# Apple_DOS_extension_board_smaller.net
KiCad netlist of a schematic drawn in EAGLE
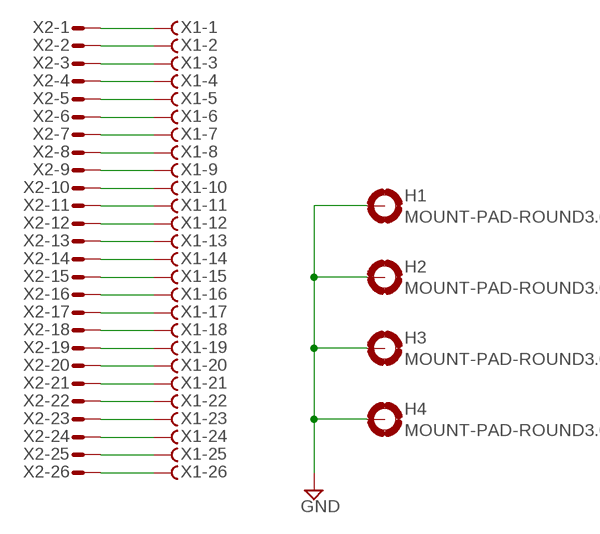
[diagram p0: schematic, sheet 1]

(export (version "E")
  (design (tool "Eeschema 10.0.6"))
  (components
    (comp (ref "H1")
      (value "MOUNT-PAD-ROUND3.6")
      (footprint "eagle-import:3,6-PAD")
      (libsource (lib "eagle-import") (part "MOUNT-PAD-ROUND3.6"))
    )
    (comp (ref "H2")
      (value "MOUNT-PAD-ROUND3.6")
      (footprint "eagle-import:3,6-PAD")
      (libsource (lib "eagle-import") (part "MOUNT-PAD-ROUND3.6"))
    )
    (comp (ref "H3")
      (value "MOUNT-PAD-ROUND3.6")
      (footprint "eagle-import:3,6-PAD")
      (libsource (lib "eagle-import") (part "MOUNT-PAD-ROUND3.6"))
    )
    (comp (ref "H4")
      (value "MOUNT-PAD-ROUND3.6")
      (footprint "eagle-import:3,6-PAD")
      (libsource (lib "eagle-import") (part "MOUNT-PAD-ROUND3.6"))
    )
    (comp (ref "X1")
      (value "HF26HS")
      (footprint "eagle-import:HDF26H")
      (libsource (lib "eagle-import") (part "HF26?SH"))
    )
    (comp (ref "X2")
      (value "HM26HS")
      (footprint "eagle-import:HDM26H")
      (libsource (lib "eagle-import") (part "HM26?SH"))
    )
  )
  (nets
    (net (code "1") (name "GND") (class "Default")
      (node (ref "H1") (pin "B3,6") (pinfunction "MOUNT_B3,6") (pintype "passive"))
      (node (ref "H2") (pin "B3,6") (pinfunction "MOUNT_B3,6") (pintype "passive"))
      (node (ref "H3") (pin "B3,6") (pinfunction "MOUNT_B3,6") (pintype "passive"))
      (node (ref "H4") (pin "B3,6") (pinfunction "MOUNT_B3,6") (pintype "passive"))
    )
    (net (code "2") (name "Net-(X1A-F)") (class "Default")
      (node (ref "X1") (pin "1") (pinfunction "F_1") (pintype "passive"))
      (node (ref "X2") (pin "1") (pinfunction "M_1") (pintype "passive"))
    )
    (net (code "3") (name "Net-(X1B-F)") (class "Default")
      (node (ref "X1") (pin "10") (pinfunction "F_10") (pintype "passive"))
      (node (ref "X2") (pin "10") (pinfunction "M_10") (pintype "passive"))
    )
    (net (code "4") (name "Net-(X1C-F)") (class "Default")
      (node (ref "X1") (pin "11") (pinfunction "F_11") (pintype "passive"))
      (node (ref "X2") (pin "11") (pinfunction "M_11") (pintype "passive"))
    )
    (net (code "5") (name "Net-(X1D-F)") (class "Default")
      (node (ref "X1") (pin "12") (pinfunction "F_12") (pintype "passive"))
      (node (ref "X2") (pin "12") (pinfunction "M_12") (pintype "passive"))
    )
    (net (code "6") (name "Net-(X1E-F)") (class "Default")
      (node (ref "X1") (pin "13") (pinfunction "F_13") (pintype "passive"))
      (node (ref "X2") (pin "13") (pinfunction "M_13") (pintype "passive"))
    )
    (net (code "7") (name "Net-(X1F-F)") (class "Default")
      (node (ref "X1") (pin "14") (pinfunction "F_14") (pintype "passive"))
      (node (ref "X2") (pin "14") (pinfunction "M_14") (pintype "passive"))
    )
    (net (code "8") (name "Net-(X1G-F)") (class "Default")
      (node (ref "X1") (pin "15") (pinfunction "F_15") (pintype "passive"))
      (node (ref "X2") (pin "15") (pinfunction "M_15") (pintype "passive"))
    )
    (net (code "9") (name "Net-(X1H-F)") (class "Default")
      (node (ref "X1") (pin "16") (pinfunction "F_16") (pintype "passive"))
      (node (ref "X2") (pin "16") (pinfunction "M_16") (pintype "passive"))
    )
    (net (code "10") (name "Net-(X1I-F)") (class "Default")
      (node (ref "X1") (pin "17") (pinfunction "F_17") (pintype "passive"))
      (node (ref "X2") (pin "17") (pinfunction "M_17") (pintype "passive"))
    )
    (net (code "11") (name "Net-(X1J-F)") (class "Default")
      (node (ref "X1") (pin "18") (pinfunction "F_18") (pintype "passive"))
      (node (ref "X2") (pin "18") (pinfunction "M_18") (pintype "passive"))
    )
    (net (code "12") (name "Net-(X1K-F)") (class "Default")
      (node (ref "X1") (pin "19") (pinfunction "F_19") (pintype "passive"))
      (node (ref "X2") (pin "19") (pinfunction "M_19") (pintype "passive"))
    )
    (net (code "13") (name "Net-(X1L-F)") (class "Default")
      (node (ref "X1") (pin "2") (pinfunction "F_2") (pintype "passive"))
      (node (ref "X2") (pin "2") (pinfunction "M_2") (pintype "passive"))
    )
    (net (code "14") (name "Net-(X1M-F)") (class "Default")
      (node (ref "X1") (pin "20") (pinfunction "F_20") (pintype "passive"))
      (node (ref "X2") (pin "20") (pinfunction "M_20") (pintype "passive"))
    )
    (net (code "15") (name "Net-(X1N-F)") (class "Default")
      (node (ref "X1") (pin "21") (pinfunction "F_21") (pintype "passive"))
      (node (ref "X2") (pin "21") (pinfunction "M_21") (pintype "passive"))
    )
    (net (code "16") (name "Net-(X1O-F)") (class "Default")
      (node (ref "X1") (pin "22") (pinfunction "F_22") (pintype "passive"))
      (node (ref "X2") (pin "22") (pinfunction "M_22") (pintype "passive"))
    )
    (net (code "17") (name "Net-(X1P-F)") (class "Default")
      (node (ref "X1") (pin "23") (pinfunction "F_23") (pintype "passive"))
      (node (ref "X2") (pin "23") (pinfunction "M_23") (pintype "passive"))
    )
    (net (code "18") (name "Net-(X1Q-F)") (class "Default")
      (node (ref "X1") (pin "24") (pinfunction "F_24") (pintype "passive"))
      (node (ref "X2") (pin "24") (pinfunction "M_24") (pintype "passive"))
    )
    (net (code "19") (name "Net-(X1R-F)") (class "Default")
      (node (ref "X1") (pin "25") (pinfunction "F_25") (pintype "passive"))
      (node (ref "X2") (pin "25") (pinfunction "M_25") (pintype "passive"))
    )
    (net (code "20") (name "Net-(X1S-F)") (class "Default")
      (node (ref "X1") (pin "26") (pinfunction "F_26") (pintype "passive"))
      (node (ref "X2") (pin "26") (pinfunction "M_26") (pintype "passive"))
    )
    (net (code "21") (name "Net-(X1T-F)") (class "Default")
      (node (ref "X1") (pin "3") (pinfunction "F_3") (pintype "passive"))
      (node (ref "X2") (pin "3") (pinfunction "M_3") (pintype "passive"))
    )
    (net (code "22") (name "Net-(X1U-F)") (class "Default")
      (node (ref "X1") (pin "4") (pinfunction "F_4") (pintype "passive"))
      (node (ref "X2") (pin "4") (pinfunction "M_4") (pintype "passive"))
    )
    (net (code "23") (name "Net-(X1V-F)") (class "Default")
      (node (ref "X1") (pin "5") (pinfunction "F_5") (pintype "passive"))
      (node (ref "X2") (pin "5") (pinfunction "M_5") (pintype "passive"))
    )
    (net (code "24") (name "Net-(X1W-F)") (class "Default")
      (node (ref "X1") (pin "6") (pinfunction "F_6") (pintype "passive"))
      (node (ref "X2") (pin "6") (pinfunction "M_6") (pintype "passive"))
    )
    (net (code "25") (name "Net-(X1X-F)") (class "Default")
      (node (ref "X1") (pin "7") (pinfunction "F_7") (pintype "passive"))
      (node (ref "X2") (pin "7") (pinfunction "M_7") (pintype "passive"))
    )
    (net (code "26") (name "Net-(X1Y-F)") (class "Default")
      (node (ref "X1") (pin "8") (pinfunction "F_8") (pintype "passive"))
      (node (ref "X2") (pin "8") (pinfunction "M_8") (pintype "passive"))
    )
    (net (code "27") (name "Net-(X1Z-F)") (class "Default")
      (node (ref "X1") (pin "9") (pinfunction "F_9") (pintype "passive"))
      (node (ref "X2") (pin "9") (pinfunction "M_9") (pintype "passive"))
    )
  )
)
